# IO.net
KiCad netlist of a schematic drawn in Altium Designer
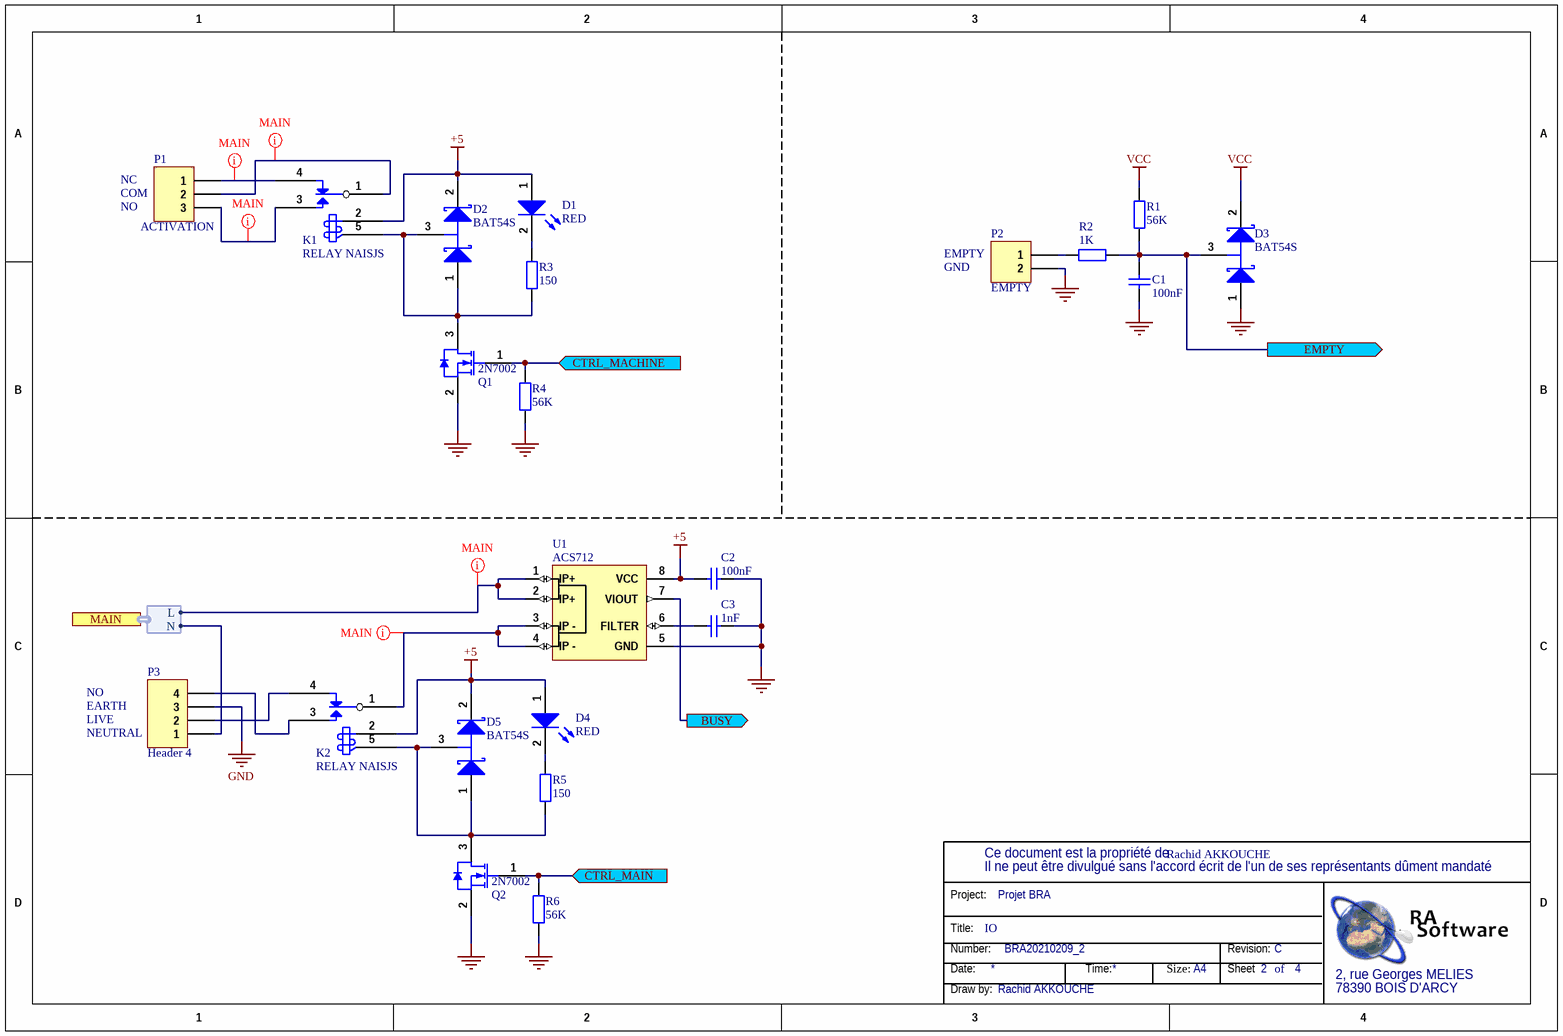
[diagram p0: IO.SchDoc]

(export (version "E")
  (design (tool "Eeschema 10.0.6"))
  (components
    (comp (ref "C1")
      (value "100nF")
      (footprint "C 0805(2012)x0.65")
      (description "Capacitor")
      (fields
        (field (name "MANUFACTURER") "MULTICOMP")
        (field (name "MANUFACTURER PART NUMBER") "MCCA000296")
      )
      (libsource (lib "BRA") (part "Cap 0805 100nF"))
    )
    (comp (ref "C2")
      (value "100nF")
      (footprint "C 0805(2012)x0.65")
      (description "Capacitor")
      (fields
        (field (name "MANUFACTURER") "MULTICOMP")
        (field (name "MANUFACTURER PART NUMBER") "MCCA000296")
      )
      (libsource (lib "BRA") (part "Cap 0805 100nF"))
    )
    (comp (ref "C3")
      (value "1nF")
      (footprint "C 0805(2012)x0.65")
      (description "Capacitor")
      (fields
        (field (name "MANUFACTURER") "SAMSUNG")
        (field (name "MANUFACTURER PART NUMBER") "CL05B102KB5NNNC")
      )
      (libsource (lib "BRA") (part "Cap 0805 1nF"))
    )
    (comp (ref "D1")
      (value "RED")
      (footprint "0603-LEDR")
      (description "Surface Mount Chip LED, Red")
      (fields
        (field (name "MANUFACTURER") "AVAGO TECHNOLOGIES")
        (field (name "MANUFACTURER PART NUMBER") "HSMH-C190.")
        (field (name "LONGUEUR/HAUTEUR") "1.6")
      )
      (libsource (lib "BRA") (part "HSMH-C190"))
    )
    (comp (ref "D2")
      (value "BAT54S")
      (footprint "SOT23")
      (description "Schottky Barrier Double Diode")
      (fields (field (name "MANUFACTURER") "MULTICOMP"))
      (libsource (lib "Ares") (part "BAT54S"))
    )
    (comp (ref "D3")
      (value "BAT54S")
      (footprint "BRA:SOT23")
      (description "Schottky Barrier Double Diode")
      (fields (field (name "MANUFACTURER") "MULTICOMP"))
      (libsource (lib "BRA") (part "BAT54S"))
    )
    (comp (ref "D4")
      (value "RED")
      (footprint "0603-LEDR")
      (description "Surface Mount Chip LED, Red")
      (fields
        (field (name "MANUFACTURER") "AVAGO TECHNOLOGIES")
        (field (name "MANUFACTURER PART NUMBER") "HSMH-C190.")
        (field (name "LONGUEUR/HAUTEUR") "1.6")
      )
      (libsource (lib "BRA") (part "HSMH-C190"))
    )
    (comp (ref "D5")
      (value "BAT54S")
      (footprint "SOT23")
      (description "Schottky Barrier Double Diode")
      (fields (field (name "MANUFACTURER") "MULTICOMP"))
      (libsource (lib "Ares") (part "BAT54S"))
    )
    (comp (ref "K1")
      (value "RELAY NAISJS")
      (footprint "RELAIG5L")
      (fields
        (field (name "MANUFACTURER") "OMRON ELECTRONIC COMPONENTS")
        (field (name "MANUFACTURER PART NUMBER") "G5LA1A412DC")
        (field (name "HAUTEUR, DIMENSION EXTERNE") "15.8")
      )
      (libsource (lib "UTIL_Library") (part "RELAY NAISJS"))
    )
    (comp (ref "K2")
      (value "RELAY NAISJS")
      (footprint "RELAIG5L")
      (fields
        (field (name "MANUFACTURER") "OMRON ELECTRONIC COMPONENTS")
        (field (name "MANUFACTURER PART NUMBER") "G5LA1A412DC")
        (field (name "HAUTEUR, DIMENSION EXTERNE") "15.8")
      )
      (libsource (lib "UTIL_Library") (part "RELAY NAISJS"))
    )
    (comp (ref "P1")
      (value "ACTIVATION")
      (footprint "CO3P381 - RIGHT")
      (description "Header, 3-Pin")
      (fields (field (name "PUBLISHER") "Altium Limited"))
      (libsource (lib "Miscellaneous Connectors") (part "Header 3"))
    )
    (comp (ref "P2")
      (value "EMPTY")
      (footprint "CO2P381-screw")
      (description "Header 2")
      (fields (field (name "PUBLISHER") "Altium Limited"))
      (libsource (lib "BRA") (part "Header 2"))
    )
    (comp (ref "P3")
      (value "Header 4")
      (footprint "CO4P508")
      (description "Header, 4-Pin")
      (fields (field (name "PUBLISHER") "Altium Limited"))
      (libsource (lib "Miscellaneous Connectors") (part "Header 4"))
    )
    (comp (ref "Q1")
      (value "2N7002")
      (footprint "SOT23")
      (description "N-channel Enhancement Mode Field-effect Transistor")
      (fields (field (name "MANUFACTURER") "FAIRCHILD SEMICONDUCTOR"))
      (libsource (lib "BRA") (part "2N7002"))
    )
    (comp (ref "Q2")
      (value "2N7002")
      (footprint "SOT23")
      (description "N-channel Enhancement Mode Field-effect Transistor")
      (fields (field (name "MANUFACTURER") "FAIRCHILD SEMICONDUCTOR"))
      (libsource (lib "BRA") (part "2N7002"))
    )
    (comp (ref "R1")
      (value "56K")
      (footprint "R 0805(2012)")
      (description "Resistor SMD 0805 56K")
      (fields
        (field (name "MANUFACTURER") "MULTICOMP")
        (field (name "MANUFACTURER PART NUMBER") "MC0.1W08051%56KFR")
      )
      (libsource (lib "BRA") (part "Resistor 0805 56K"))
    )
    (comp (ref "R2")
      (value "1K")
      (footprint "R 0805(2012)")
      (description "Resistor SMD 0805 1K")
      (fields
        (field (name "MANUFACTURER") "MULTICOMP")
        (field (name "MANUFACTURER PART NUMBER") "MC0.1W08051%1KFR")
      )
      (libsource (lib "BRA") (part "Resistor 0805 1K"))
    )
    (comp (ref "R3")
      (value "150")
      (footprint "R 0805(2012)")
      (description "Resistor SMD 0805 150")
      (fields
        (field (name "MANUFACTURER") "YAGEO")
        (field (name "MANUFACTURER PART NUMBER") "RC0805JR-07150KL")
      )
      (libsource (lib "BRA") (part "Resistor 0805 150"))
    )
    (comp (ref "R4")
      (value "56K")
      (footprint "R 0805(2012)")
      (description "Resistor")
      (fields
        (field (name "MANUFACTURER") "MULTICOMP")
        (field (name "MANUFACTURER PART NUMBER") "MC0.1W08051%56KFR")
      )
      (libsource (lib "BRA") (part "Resistor 0805 56K"))
    )
    (comp (ref "R5")
      (value "150")
      (footprint "R 0805(2012)")
      (description "Resistor SMD 0805 150")
      (fields
        (field (name "MANUFACTURER") "YAGEO")
        (field (name "MANUFACTURER PART NUMBER") "RC0805JR-07150KL")
      )
      (libsource (lib "BRA") (part "Resistor 0805 150"))
    )
    (comp (ref "R6")
      (value "56K")
      (footprint "R 0805(2012)")
      (description "Resistor")
      (fields
        (field (name "MANUFACTURER") "MULTICOMP")
        (field (name "MANUFACTURER PART NUMBER") "MC0.1W08051%56KFR")
      )
      (libsource (lib "BRA") (part "Resistor 0805 56K"))
    )
    (comp (ref "U1")
      (value "ACS712")
      (footprint "SOIC8")
      (description "HALL EFFECT CURRENT SENSOR")
      (fields
        (field (name "MANUFACTURER") "ALLEGRO MICROSYSTEMS")
        (field (name "MANUFACTURER PART NUMBER") "ACS712ELCTR-20A-T")
      )
      (libsource (lib "BRA") (part "ACS712"))
    )
  )
  (nets
    (net (code "2") (name "+5") (class "Default")
      (node (ref "C2") (pin "2") (pinfunction "2_2") (pintype "passive"))
      (node (ref "D1") (pin "1") (pinfunction "A_1") (pintype "passive"))
      (node (ref "D2") (pin "2") (pinfunction "K_2") (pintype "passive"))
      (node (ref "D4") (pin "1") (pinfunction "A_1") (pintype "passive"))
      (node (ref "D5") (pin "2") (pinfunction "K_2") (pintype "passive"))
      (node (ref "K1") (pin "2") (pinfunction "COIL1_2") (pintype "passive"))
      (node (ref "K2") (pin "2") (pinfunction "COIL1_2") (pintype "passive"))
      (node (ref "U1") (pin "8") (pinfunction "VCC_8") (pintype "power_in"))
    )
    (net (code "3") (name "/BUSY") (class "Default")
      (node (ref "U1") (pin "7") (pinfunction "VIOUT_7") (pintype "output"))
    )
    (net (code "4") (name "/CTRL_MACHINE") (class "Default")
      (node (ref "Q1") (pin "1") (pinfunction "G_1") (pintype "passive"))
      (node (ref "R4") (pin "2") (pinfunction "2_2") (pintype "passive"))
    )
    (net (code "5") (name "/CTRL_MAIN") (class "Default")
      (node (ref "Q2") (pin "1") (pinfunction "G_1") (pintype "passive"))
      (node (ref "R6") (pin "2") (pinfunction "2_2") (pintype "passive"))
    )
    (net (code "6") (name "/EMPTY") (class "Default")
      (node (ref "C1") (pin "2") (pinfunction "2_2") (pintype "passive"))
      (node (ref "D3") (pin "3") (pinfunction "C_3") (pintype "passive"))
      (node (ref "R1") (pin "1") (pinfunction "1_1") (pintype "passive"))
      (node (ref "R2") (pin "1") (pinfunction "1_1") (pintype "passive"))
    )
    (net (code "7") (name "/L") (class "Default")
      (node (ref "U1") (pin "1") (pinfunction "IP+_1") (pintype "bidirectional"))
      (node (ref "U1") (pin "2") (pinfunction "IP+_2") (pintype "bidirectional"))
    )
    (net (code "8") (name "/N") (class "Default")
      (node (ref "P3") (pin "1") (pinfunction "1_1") (pintype "passive"))
    )
    (net (code "10") (name "GND") (class "Default")
      (node (ref "C1") (pin "1") (pinfunction "1_1") (pintype "passive"))
      (node (ref "C2") (pin "1") (pinfunction "1_1") (pintype "passive"))
      (node (ref "C3") (pin "2") (pinfunction "2_2") (pintype "passive"))
      (node (ref "D3") (pin "1") (pinfunction "A_1") (pintype "passive"))
      (node (ref "P2") (pin "2") (pinfunction "2_2") (pintype "passive"))
      (node (ref "P3") (pin "3") (pinfunction "3_3") (pintype "passive"))
      (node (ref "Q1") (pin "2") (pinfunction "S_2") (pintype "passive"))
      (node (ref "Q2") (pin "2") (pinfunction "S_2") (pintype "passive"))
      (node (ref "R4") (pin "1") (pinfunction "1_1") (pintype "passive"))
      (node (ref "R6") (pin "1") (pinfunction "1_1") (pintype "passive"))
      (node (ref "U1") (pin "5") (pinfunction "GND_5") (pintype "power_in"))
    )
    (net (code "11") (name "Net-(D1-K)") (class "Default")
      (node (ref "D1") (pin "2") (pinfunction "K_2") (pintype "passive"))
      (node (ref "R3") (pin "2") (pinfunction "2_2") (pintype "passive"))
    )
    (net (code "12") (name "Net-(D2-A)") (class "Default")
      (node (ref "D2") (pin "1") (pinfunction "A_1") (pintype "passive"))
      (node (ref "D2") (pin "3") (pinfunction "C_3") (pintype "passive"))
      (node (ref "K1") (pin "5") (pinfunction "COIL2_5") (pintype "passive"))
      (node (ref "Q1") (pin "3") (pinfunction "D_3") (pintype "passive"))
      (node (ref "R3") (pin "1") (pinfunction "1_1") (pintype "passive"))
    )
    (net (code "13") (name "Net-(D4-K)") (class "Default")
      (node (ref "D4") (pin "2") (pinfunction "K_2") (pintype "passive"))
      (node (ref "R5") (pin "2") (pinfunction "2_2") (pintype "passive"))
    )
    (net (code "14") (name "Net-(D5-A)") (class "Default")
      (node (ref "D5") (pin "1") (pinfunction "A_1") (pintype "passive"))
      (node (ref "D5") (pin "3") (pinfunction "C_3") (pintype "passive"))
      (node (ref "K2") (pin "5") (pinfunction "COIL2_5") (pintype "passive"))
      (node (ref "Q2") (pin "3") (pinfunction "D_3") (pintype "passive"))
      (node (ref "R5") (pin "1") (pinfunction "1_1") (pintype "passive"))
    )
    (net (code "15") (name "Net-(K1-COMMON)") (class "Default")
      (node (ref "K1") (pin "1") (pinfunction "COMMON_1") (pintype "passive"))
      (node (ref "P1") (pin "2") (pinfunction "2_2") (pintype "passive"))
    )
    (net (code "16") (name "Net-(K1-NC)") (class "Default")
      (node (ref "K1") (pin "4") (pinfunction "NC_4") (pintype "passive"))
      (node (ref "P1") (pin "1") (pinfunction "1_1") (pintype "passive"))
    )
    (net (code "17") (name "Net-(K1-NO)") (class "Default")
      (node (ref "K1") (pin "3") (pinfunction "NO_3") (pintype "passive"))
      (node (ref "P1") (pin "3") (pinfunction "3_3") (pintype "passive"))
    )
    (net (code "18") (name "Net-(K2-COMMON)") (class "Default")
      (node (ref "K2") (pin "1") (pinfunction "COMMON_1") (pintype "passive"))
      (node (ref "U1") (pin "3") (pinfunction "IP_-_3") (pintype "bidirectional"))
      (node (ref "U1") (pin "4") (pinfunction "IP_-_4") (pintype "bidirectional"))
    )
    (net (code "19") (name "Net-(K2-NC)") (class "Default")
      (node (ref "K2") (pin "4") (pinfunction "NC_4") (pintype "passive"))
      (node (ref "P3") (pin "2") (pinfunction "2_2") (pintype "passive"))
    )
    (net (code "20") (name "Net-(K2-NO)") (class "Default")
      (node (ref "K2") (pin "3") (pinfunction "NO_3") (pintype "passive"))
      (node (ref "P3") (pin "4") (pinfunction "4_4") (pintype "passive"))
    )
    (net (code "21") (name "Net-(P2-Pad1)") (class "Default")
      (node (ref "P2") (pin "1") (pinfunction "1_1") (pintype "passive"))
      (node (ref "R2") (pin "2") (pinfunction "2_2") (pintype "passive"))
    )
    (net (code "22") (name "Net-(U1-FILTER)") (class "Default")
      (node (ref "C3") (pin "1") (pinfunction "1_1") (pintype "passive"))
      (node (ref "U1") (pin "6") (pinfunction "FILTER_6") (pintype "bidirectional"))
    )
    (net (code "23") (name "VCC") (class "Default")
      (node (ref "D3") (pin "2") (pinfunction "K_2") (pintype "passive"))
      (node (ref "R1") (pin "2") (pinfunction "2_2") (pintype "passive"))
    )
  )
)
